# low_voltage_rails.net
KiCad netlist of a schematic drawn in Altium Designer
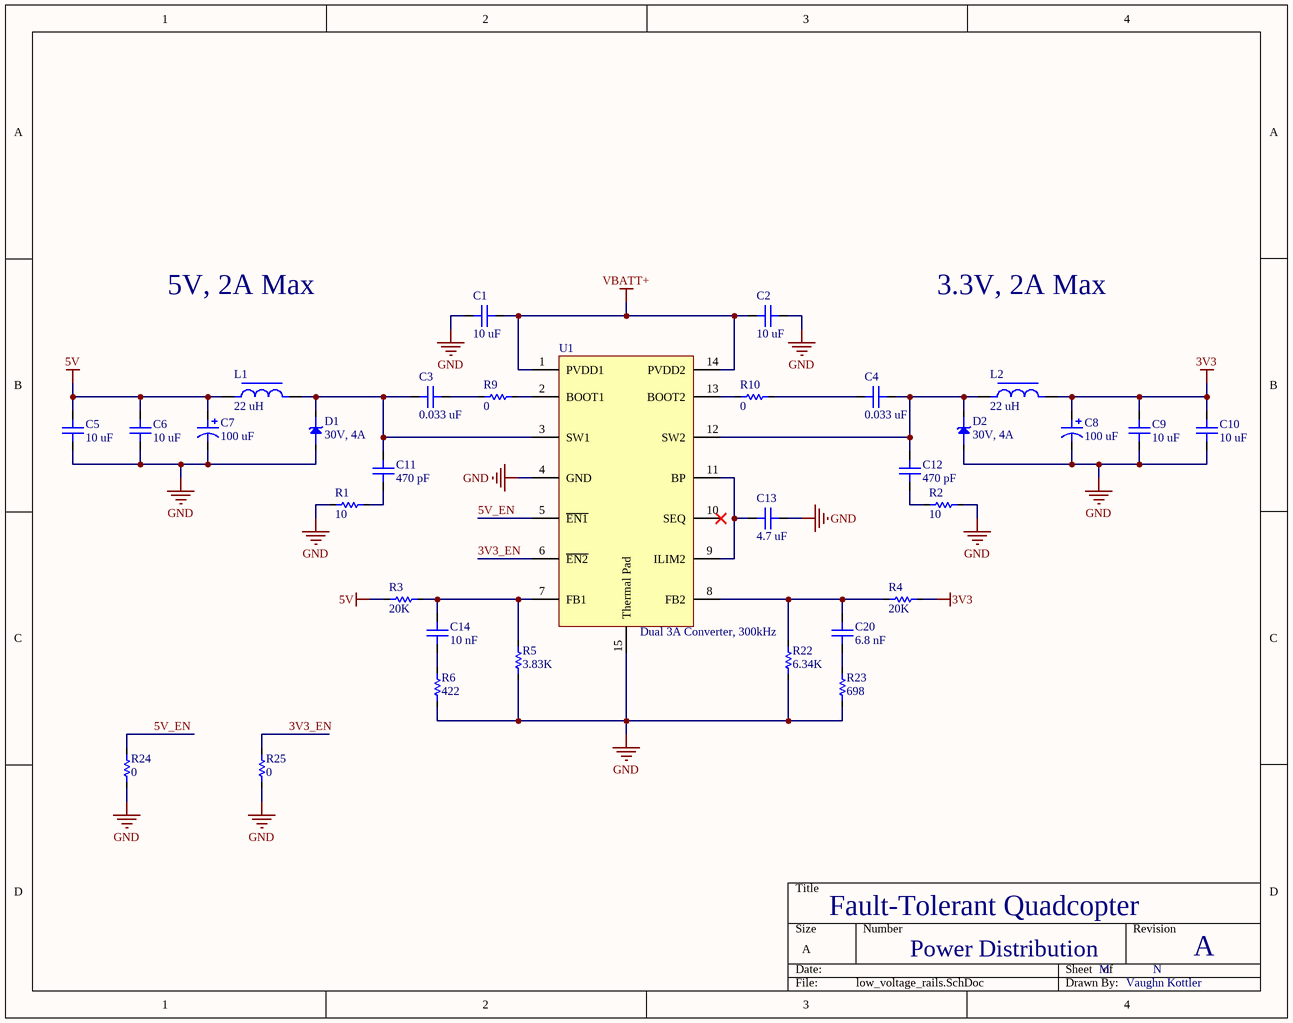
[diagram p0: low_voltage_rails.SchDoc]

(export (version "E")
  (design (tool "Eeschema 10.0.6"))
  (components
    (comp (ref "C1")
      (value "10 uF")
      (footprint "CAP-CER-1206")
      (description "±20%, 1206")
      (libsource (lib "passive") (part "CAP-CER-10uF-25V-1206"))
    )
    (comp (ref "C2")
      (value "10 uF")
      (footprint "CAP-CER-1206")
      (description "±20%, 1206")
      (libsource (lib "passive") (part "CAP-CER-10uF-25V-1206"))
    )
    (comp (ref "C3")
      (value "0.033 uF")
      (footprint "CAP-CER-0603")
      (description "10%, 0603")
      (libsource (lib "passive") (part "CAP-CER-0.033uF-25V"))
    )
    (comp (ref "C4")
      (value "0.033 uF")
      (footprint "CAP-CER-0603")
      (description "10%, 0603")
      (libsource (lib "passive") (part "CAP-CER-0.033uF-25V"))
    )
    (comp (ref "C5")
      (value "10 uF")
      (footprint "CAP-CER-0805-TALL")
      (description "±10%, 0805")
      (libsource (lib "passive") (part "CAP-CER-10uF-25V"))
    )
    (comp (ref "C6")
      (value "10 uF")
      (footprint "CAP-CER-0805-TALL")
      (description "±10%, 0805")
      (libsource (lib "passive") (part "CAP-CER-10uF-25V"))
    )
    (comp (ref "C7")
      (value "100 uF")
      (footprint "CAP-CAN-8.3x8.3")
      (description "±20%, 8.3mm x 8.3mm")
      (libsource (lib "passive") (part "CAP-CAN-100uF-10V"))
    )
    (comp (ref "C8")
      (value "100 uF")
      (footprint "CAP-CAN-8.3x8.3")
      (description "±20%, 8.3mm x 8.3mm")
      (libsource (lib "passive") (part "CAP-CAN-100uF-10V"))
    )
    (comp (ref "C9")
      (value "10 uF")
      (footprint "CAP-CER-0805-TALL")
      (description "±10%, 0805")
      (libsource (lib "passive") (part "CAP-CER-10uF-25V"))
    )
    (comp (ref "C10")
      (value "10 uF")
      (footprint "CAP-CER-0805-TALL")
      (description "±10%, 0805")
      (libsource (lib "passive") (part "CAP-CER-10uF-25V"))
    )
    (comp (ref "C11")
      (value "470 pF")
      (footprint "CAP-CER-0603")
      (description "20%, 0603")
      (libsource (lib "passive") (part "CAP-CER-470pF-50V"))
    )
    (comp (ref "C12")
      (value "470 pF")
      (footprint "CAP-CER-0603")
      (description "20%, 0603")
      (libsource (lib "passive") (part "CAP-CER-470pF-50V"))
    )
    (comp (ref "C13")
      (value "4.7 uF")
      (footprint "CAP-CER-0805-TALL")
      (description "±10%, 0805")
      (libsource (lib "passive") (part "CAP-CER-4.7uF-10V"))
    )
    (comp (ref "C14")
      (value "10 nF")
      (footprint "CAP-CER-0603")
      (description "±20%, 0603")
      (libsource (lib "passive") (part "CAP-CER-10nF-25V"))
    )
    (comp (ref "C20")
      (value "6.8 nF")
      (footprint "CAP-CER-0603")
      (description "±10%, 0603")
      (libsource (lib "passive") (part "CAP-CER-6.8nF-25V"))
    )
    (comp (ref "D1")
      (value "30V, 4A")
      (footprint "DO-214AB-SMC")
      (description "Schottky, SMC (DO-214AB)")
      (libsource (lib "passive") (part "DIO-500mV-30V-4A"))
    )
    (comp (ref "D2")
      (value "30V, 4A")
      (footprint "DO-214AB-SMC")
      (description "Schottky, SMC (DO-214AB)")
      (libsource (lib "passive") (part "DIO-500mV-30V-4A"))
    )
    (comp (ref "L1")
      (value "22 uH")
      (footprint "IND-12mm")
      (description "±20%, 8 MHz res")
      (libsource (lib "passive") (part "IND-22uH-38m-5.2A"))
    )
    (comp (ref "L2")
      (value "22 uH")
      (footprint "IND-12mm")
      (description "±20%, 8 MHz res")
      (libsource (lib "passive") (part "IND-22uH-38m-5.2A"))
    )
    (comp (ref "R1")
      (value "10")
      (footprint "RES-0603")
      (description "5%, 0603")
      (libsource (lib "passive") (part "RES-10-1/4W"))
    )
    (comp (ref "R2")
      (value "10")
      (footprint "RES-0603")
      (description "5%, 0603")
      (libsource (lib "passive") (part "RES-10-1/4W"))
    )
    (comp (ref "R3")
      (value "20K")
      (footprint "RES-0603")
      (description "1%, 0603")
      (libsource (lib "passive") (part "RES-20K-1/10W"))
    )
    (comp (ref "R4")
      (value "20K")
      (footprint "RES-0603")
      (description "1%, 0603")
      (libsource (lib "passive") (part "RES-20K-1/10W"))
    )
    (comp (ref "R5")
      (value "3.83K")
      (footprint "RES-0603")
      (description "1%, 0603")
      (libsource (lib "passive") (part "RES-3.83K-1/10W"))
    )
    (comp (ref "R6")
      (value "422")
      (footprint "RES-0603")
      (description "1%, 0603")
      (libsource (lib "passive") (part "RES-422-1/10W"))
    )
    (comp (ref "R9")
      (value "0")
      (footprint "RES-0603")
      (description "0603")
      (libsource (lib "passive") (part "RES-0-1/10W"))
    )
    (comp (ref "R10")
      (value "0")
      (footprint "RES-0603")
      (description "0603")
      (libsource (lib "passive") (part "RES-0-1/10W"))
    )
    (comp (ref "R22")
      (value "6.34K")
      (footprint "RES-0603")
      (description "1%, 0603")
      (libsource (lib "passive") (part "RES-6.34K-1/10W"))
    )
    (comp (ref "R23")
      (value "698")
      (footprint "RES-0603")
      (description "1%, 0603")
      (libsource (lib "passive") (part "RES-698-1/10W"))
    )
    (comp (ref "R24")
      (value "0")
      (footprint "RES-0805")
      (description "0805")
      (libsource (lib "passive") (part "RES-0-1/8W"))
    )
    (comp (ref "R25")
      (value "0")
      (footprint "RES-0805")
      (description "0805")
      (libsource (lib "passive") (part "RES-0-1/8W"))
    )
    (comp (ref "U1")
      (value "Dual 3A Converter, 300kHz")
      (footprint "14-HTSSOP")
      (description "Dual 3A Non-Synchronous Converters with Integrated High-Side MOSFET")
      (libsource (lib "ic") (part "TPS54383"))
    )
  )
  (nets
    (net (code "1") (name "/3V3_EN") (class "Default")
      (node (ref "R25") (pin "2") (pinfunction "2_2") (pintype "passive"))
      (node (ref "U1") (pin "6") (pinfunction "~{EN2}_6") (pintype "passive"))
    )
    (net (code "2") (name "/5V_EN") (class "Default")
      (node (ref "R24") (pin "2") (pinfunction "2_2") (pintype "passive"))
      (node (ref "U1") (pin "5") (pinfunction "~{EN1}_5") (pintype "passive"))
    )
    (net (code "3") (name "3V3") (class "Default")
      (node (ref "C10") (pin "2") (pinfunction "2_2") (pintype "passive"))
      (node (ref "C8") (pin "1") (pinfunction "1_1") (pintype "passive"))
      (node (ref "C9") (pin "2") (pinfunction "2_2") (pintype "passive"))
      (node (ref "L2") (pin "2") (pinfunction "2_2") (pintype "passive"))
      (node (ref "R4") (pin "2") (pinfunction "2_2") (pintype "passive"))
    )
    (net (code "4") (name "5V") (class "Default")
      (node (ref "C5") (pin "2") (pinfunction "2_2") (pintype "passive"))
      (node (ref "C6") (pin "2") (pinfunction "2_2") (pintype "passive"))
      (node (ref "C7") (pin "1") (pinfunction "1_1") (pintype "passive"))
      (node (ref "L1") (pin "1") (pinfunction "1_1") (pintype "passive"))
      (node (ref "R3") (pin "1") (pinfunction "1_1") (pintype "passive"))
    )
    (net (code "5") (name "GND") (class "Default")
      (node (ref "C1") (pin "1") (pinfunction "1_1") (pintype "passive"))
      (node (ref "C10") (pin "1") (pinfunction "1_1") (pintype "passive"))
      (node (ref "C13") (pin "1") (pinfunction "1_1") (pintype "passive"))
      (node (ref "C2") (pin "2") (pinfunction "2_2") (pintype "passive"))
      (node (ref "C5") (pin "1") (pinfunction "1_1") (pintype "passive"))
      (node (ref "C6") (pin "1") (pinfunction "1_1") (pintype "passive"))
      (node (ref "C7") (pin "2") (pinfunction "2_2") (pintype "passive"))
      (node (ref "C8") (pin "2") (pinfunction "2_2") (pintype "passive"))
      (node (ref "C9") (pin "1") (pinfunction "1_1") (pintype "passive"))
      (node (ref "D1") (pin "1") (pinfunction "CT_1") (pintype "passive"))
      (node (ref "D2") (pin "1") (pinfunction "CT_1") (pintype "passive"))
      (node (ref "R1") (pin "2") (pinfunction "2_2") (pintype "passive"))
      (node (ref "R2") (pin "1") (pinfunction "1_1") (pintype "passive"))
      (node (ref "R22") (pin "1") (pinfunction "1_1") (pintype "passive"))
      (node (ref "R23") (pin "1") (pinfunction "1_1") (pintype "passive"))
      (node (ref "R24") (pin "1") (pinfunction "1_1") (pintype "passive"))
      (node (ref "R25") (pin "1") (pinfunction "1_1") (pintype "passive"))
      (node (ref "R5") (pin "1") (pinfunction "1_1") (pintype "passive"))
      (node (ref "R6") (pin "1") (pinfunction "1_1") (pintype "passive"))
      (node (ref "U1") (pin "15") (pinfunction "Thermal_Pad_15") (pintype "passive"))
      (node (ref "U1") (pin "4") (pinfunction "GND_4") (pintype "passive"))
    )
    (net (code "6") (name "Net-(C3-Pad2)") (class "Default")
      (node (ref "C3") (pin "2") (pinfunction "2_2") (pintype "passive"))
      (node (ref "R9") (pin "1") (pinfunction "1_1") (pintype "passive"))
    )
    (net (code "7") (name "Net-(C4-Pad1)") (class "Default")
      (node (ref "C4") (pin "1") (pinfunction "1_1") (pintype "passive"))
      (node (ref "R10") (pin "2") (pinfunction "2_2") (pintype "passive"))
    )
    (net (code "8") (name "Net-(C11-Pad1)") (class "Default")
      (node (ref "C11") (pin "1") (pinfunction "1_1") (pintype "passive"))
      (node (ref "R1") (pin "1") (pinfunction "1_1") (pintype "passive"))
    )
    (net (code "9") (name "Net-(C12-Pad1)") (class "Default")
      (node (ref "C12") (pin "1") (pinfunction "1_1") (pintype "passive"))
      (node (ref "R2") (pin "2") (pinfunction "2_2") (pintype "passive"))
    )
    (net (code "10") (name "Net-(C14-Pad1)") (class "Default")
      (node (ref "C14") (pin "1") (pinfunction "1_1") (pintype "passive"))
      (node (ref "R6") (pin "2") (pinfunction "2_2") (pintype "passive"))
    )
    (net (code "11") (name "Net-(C20-Pad1)") (class "Default")
      (node (ref "C20") (pin "1") (pinfunction "1_1") (pintype "passive"))
      (node (ref "R23") (pin "2") (pinfunction "2_2") (pintype "passive"))
    )
    (net (code "12") (name "Net-(D1-AN)") (class "Default")
      (node (ref "C11") (pin "2") (pinfunction "2_2") (pintype "passive"))
      (node (ref "C3") (pin "1") (pinfunction "1_1") (pintype "passive"))
      (node (ref "D1") (pin "2") (pinfunction "AN_2") (pintype "passive"))
      (node (ref "L1") (pin "2") (pinfunction "2_2") (pintype "passive"))
      (node (ref "U1") (pin "3") (pinfunction "SW1_3") (pintype "passive"))
    )
    (net (code "13") (name "Net-(D2-AN)") (class "Default")
      (node (ref "C12") (pin "2") (pinfunction "2_2") (pintype "passive"))
      (node (ref "C4") (pin "2") (pinfunction "2_2") (pintype "passive"))
      (node (ref "D2") (pin "2") (pinfunction "AN_2") (pintype "passive"))
      (node (ref "L2") (pin "1") (pinfunction "1_1") (pintype "passive"))
      (node (ref "U1") (pin "12") (pinfunction "SW2_12") (pintype "passive"))
    )
    (net (code "14") (name "Net-(U1-BOOT1)") (class "Default")
      (node (ref "R9") (pin "2") (pinfunction "2_2") (pintype "passive"))
      (node (ref "U1") (pin "2") (pinfunction "BOOT1_2") (pintype "passive"))
    )
    (net (code "15") (name "Net-(U1-BOOT2)") (class "Default")
      (node (ref "R10") (pin "1") (pinfunction "1_1") (pintype "passive"))
      (node (ref "U1") (pin "13") (pinfunction "BOOT2_13") (pintype "passive"))
    )
    (net (code "16") (name "Net-(U1-BP)") (class "Default")
      (node (ref "C13") (pin "2") (pinfunction "2_2") (pintype "passive"))
      (node (ref "U1") (pin "11") (pinfunction "BP_11") (pintype "passive"))
      (node (ref "U1") (pin "9") (pinfunction "ILIM2_9") (pintype "passive"))
    )
    (net (code "17") (name "Net-(U1-FB1)") (class "Default")
      (node (ref "C14") (pin "2") (pinfunction "2_2") (pintype "passive"))
      (node (ref "R3") (pin "2") (pinfunction "2_2") (pintype "passive"))
      (node (ref "R5") (pin "2") (pinfunction "2_2") (pintype "passive"))
      (node (ref "U1") (pin "7") (pinfunction "FB1_7") (pintype "passive"))
    )
    (net (code "18") (name "Net-(U1-FB2)") (class "Default")
      (node (ref "C20") (pin "2") (pinfunction "2_2") (pintype "passive"))
      (node (ref "R22") (pin "2") (pinfunction "2_2") (pintype "passive"))
      (node (ref "R4") (pin "1") (pinfunction "1_1") (pintype "passive"))
      (node (ref "U1") (pin "8") (pinfunction "FB2_8") (pintype "passive"))
    )
    (net (code "19") (name "VBATT+") (class "Default")
      (node (ref "C1") (pin "2") (pinfunction "2_2") (pintype "passive"))
      (node (ref "C2") (pin "1") (pinfunction "1_1") (pintype "passive"))
      (node (ref "U1") (pin "1") (pinfunction "PVDD1_1") (pintype "passive"))
      (node (ref "U1") (pin "14") (pinfunction "PVDD2_14") (pintype "passive"))
    )
    (net (code "20") (name "unconnected-(U1-SEQ-Pad10)") (class "Default")
      (node (ref "U1") (pin "10") (pinfunction "SEQ_10") (pintype "passive+no_connect"))
    )
  )
)
